# addon.net
KiCad netlist of a schematic drawn in EAGLE
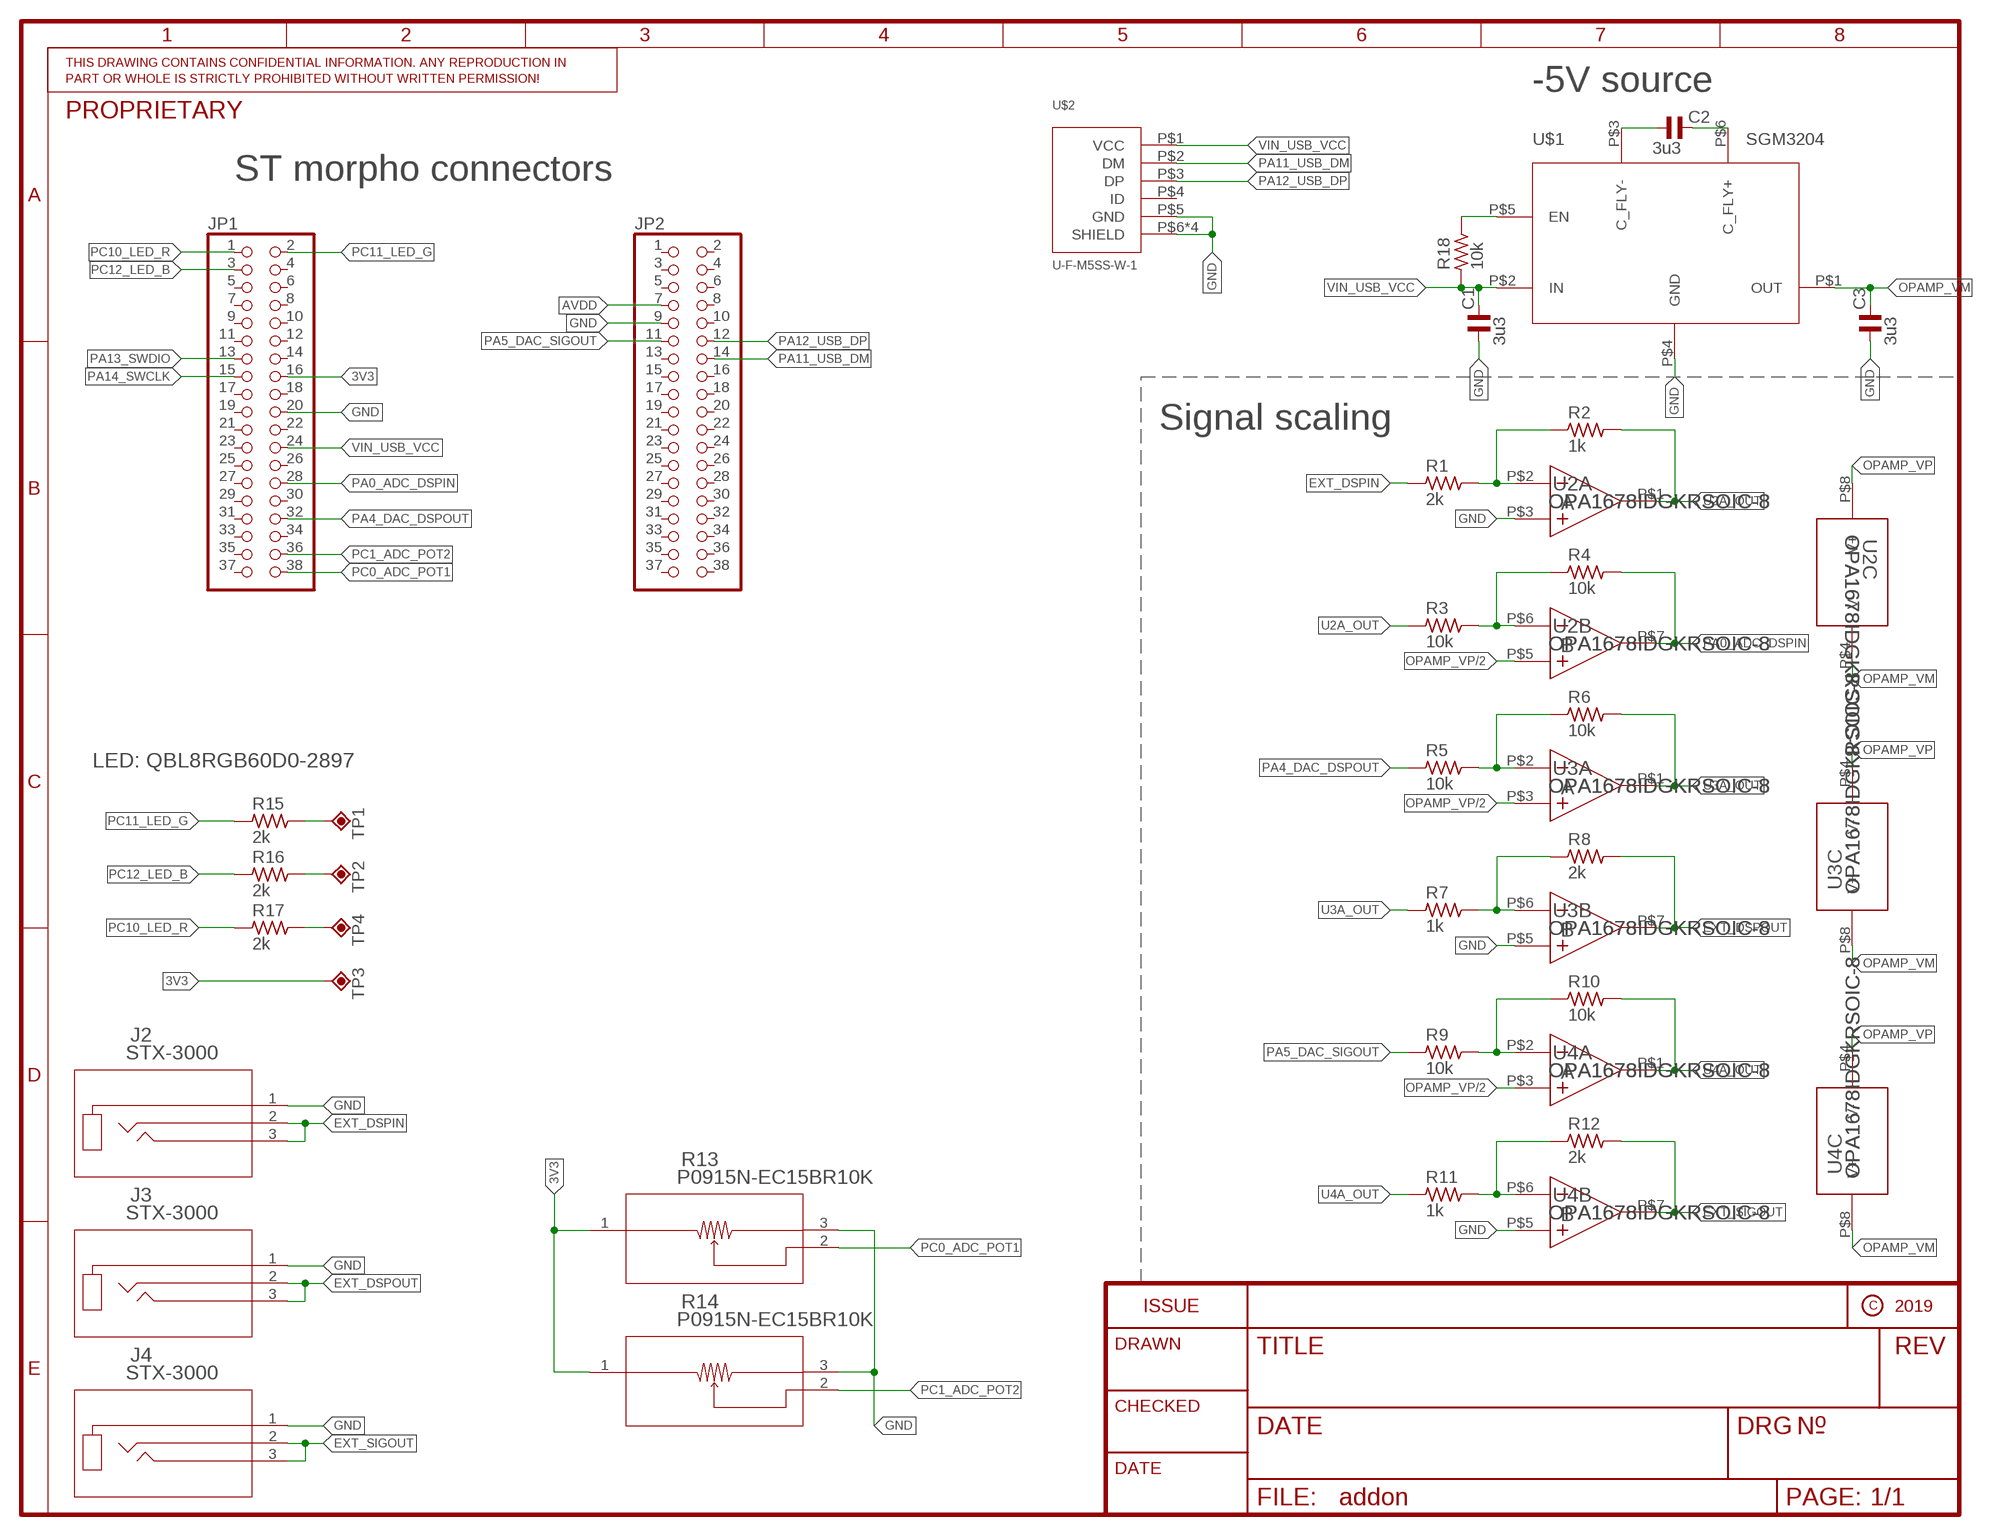
[diagram p0: schematic, sheet 1]

(export (version "E")
  (design (tool "Eeschema 10.0.6"))
  (components
    (comp (ref "C1")
      (value "3u3")
      (footprint "eagle-import:C0603")
      (fields (field (name "PARTNO") "CL10A335KP8NNNC"))
      (libsource (lib "eagle-import") (part "C_0603"))
    )
    (comp (ref "C2")
      (value "3u3")
      (footprint "eagle-import:C0603")
      (fields (field (name "PARTNO") "CL10A335KP8NNNC"))
      (libsource (lib "eagle-import") (part "C_0603"))
    )
    (comp (ref "C3")
      (value "3u3")
      (footprint "eagle-import:C0603")
      (fields (field (name "PARTNO") "CL10A335KP8NNNC"))
      (libsource (lib "eagle-import") (part "C_0603"))
    )
    (comp (ref "J2")
      (value "STX-3000")
      (footprint "eagle-import:STX-3000_KYC")
      (fields (field (name "COPYRIGHT") "Copyright (C) 2018 Accelerated Designs. All rights reserved"))
      (libsource (lib "eagle-import") (part "STX-3000"))
    )
    (comp (ref "J3")
      (value "STX-3000")
      (footprint "eagle-import:STX-3000_KYC")
      (fields (field (name "COPYRIGHT") "Copyright (C) 2018 Accelerated Designs. All rights reserved"))
      (libsource (lib "eagle-import") (part "STX-3000"))
    )
    (comp (ref "J4")
      (value "STX-3000")
      (footprint "eagle-import:STX-3000_KYC")
      (fields (field (name "COPYRIGHT") "Copyright (C) 2018 Accelerated Designs. All rights reserved"))
      (libsource (lib "eagle-import") (part "STX-3000"))
    )
    (comp (ref "JP1")
      (value "PINHD-2X19")
      (footprint "eagle-import:2X19")
      (libsource (lib "eagle-import") (part "PINHD-2X19"))
    )
    (comp (ref "JP2")
      (value "PINHD-2X19")
      (footprint "eagle-import:2X19")
      (libsource (lib "eagle-import") (part "PINHD-2X19"))
    )
    (comp (ref "R1")
      (value "2k")
      (footprint "eagle-import:R0603")
      (libsource (lib "eagle-import") (part "R_0603"))
    )
    (comp (ref "R2")
      (value "1k")
      (footprint "eagle-import:R0603")
      (libsource (lib "eagle-import") (part "R_0603"))
    )
    (comp (ref "R3")
      (value "10k")
      (footprint "eagle-import:R0603")
      (libsource (lib "eagle-import") (part "R_0603"))
    )
    (comp (ref "R4")
      (value "10k")
      (footprint "eagle-import:R0603")
      (libsource (lib "eagle-import") (part "R_0603"))
    )
    (comp (ref "R5")
      (value "10k")
      (footprint "eagle-import:R0603")
      (libsource (lib "eagle-import") (part "R_0603"))
    )
    (comp (ref "R6")
      (value "10k")
      (footprint "eagle-import:R0603")
      (libsource (lib "eagle-import") (part "R_0603"))
    )
    (comp (ref "R7")
      (value "1k")
      (footprint "eagle-import:R0603")
      (libsource (lib "eagle-import") (part "R_0603"))
    )
    (comp (ref "R8")
      (value "2k")
      (footprint "eagle-import:R0603")
      (libsource (lib "eagle-import") (part "R_0603"))
    )
    (comp (ref "R9")
      (value "10k")
      (footprint "eagle-import:R0603")
      (libsource (lib "eagle-import") (part "R_0603"))
    )
    (comp (ref "R10")
      (value "10k")
      (footprint "eagle-import:R0603")
      (libsource (lib "eagle-import") (part "R_0603"))
    )
    (comp (ref "R11")
      (value "1k")
      (footprint "eagle-import:R0603")
      (libsource (lib "eagle-import") (part "R_0603"))
    )
    (comp (ref "R12")
      (value "2k")
      (footprint "eagle-import:R0603")
      (libsource (lib "eagle-import") (part "R_0603"))
    )
    (comp (ref "R13")
      (value "P0915N-EC15BR10K")
      (footprint "eagle-import:P0915N-EC15BR10K_BIT")
      (fields (field (name "COPYRIGHT") "Copyright (C) 2018 Accelerated Designs. All rights reserved"))
      (libsource (lib "eagle-import") (part "P0915N-EC15BR10K"))
    )
    (comp (ref "R14")
      (value "P0915N-EC15BR10K")
      (footprint "eagle-import:P0915N-EC15BR10K_BIT")
      (fields (field (name "COPYRIGHT") "Copyright (C) 2018 Accelerated Designs. All rights reserved"))
      (libsource (lib "eagle-import") (part "P0915N-EC15BR10K"))
    )
    (comp (ref "R15")
      (value "2k")
      (footprint "eagle-import:R0603")
      (libsource (lib "eagle-import") (part "R_0603"))
    )
    (comp (ref "R16")
      (value "2k")
      (footprint "eagle-import:R0603")
      (libsource (lib "eagle-import") (part "R_0603"))
    )
    (comp (ref "R17")
      (value "2k")
      (footprint "eagle-import:R0603")
      (libsource (lib "eagle-import") (part "R_0603"))
    )
    (comp (ref "R18")
      (value "10k")
      (footprint "eagle-import:R0603")
      (libsource (lib "eagle-import") (part "rc-master-smd_R_0603"))
    )
    (comp (ref "TP1")
      (value "TPP-5000-M")
      (footprint "eagle-import:5000-M")
      (libsource (lib "eagle-import") (part "TPP-5000-M"))
    )
    (comp (ref "TP2")
      (value "TPP-5000-M")
      (footprint "eagle-import:5000-M")
      (libsource (lib "eagle-import") (part "TPP-5000-M"))
    )
    (comp (ref "TP3")
      (value "TPP-5000-M")
      (footprint "eagle-import:5000-M")
      (libsource (lib "eagle-import") (part "TPP-5000-M"))
    )
    (comp (ref "TP4")
      (value "TPP-5000-M")
      (footprint "eagle-import:5000-M")
      (libsource (lib "eagle-import") (part "TPP-5000-M"))
    )
    (comp (ref "U$1")
      (value "SGM3204")
      (footprint "eagle-import:SOT-23-6")
      (fields (field (name "PARTNO") "SGM3204YN6G/TR"))
      (libsource (lib "eagle-import") (part "SGM3204"))
    )
    (comp (ref "U$2")
      (value "U-F-M5SS-W-1")
      (footprint "eagle-import:MICRO-B-USB")
      (libsource (lib "eagle-import") (part "U-F-M5SS-W-1"))
    )
    (comp (ref "U2")
      (value "OPA1678IDGKRSOIC-8")
      (footprint "eagle-import:SOIC-8")
      (fields (field (name "PARTNO") "NE5532DR"))
      (libsource (lib "eagle-import") (part "OPA1678IDGKRSOIC-8"))
    )
    (comp (ref "U3")
      (value "OPA1678IDGKRSOIC-8")
      (footprint "eagle-import:SOIC-8")
      (fields (field (name "PARTNO") "NE5532DR"))
      (libsource (lib "eagle-import") (part "OPA1678IDGKRSOIC-8"))
    )
    (comp (ref "U4")
      (value "OPA1678IDGKRSOIC-8")
      (footprint "eagle-import:SOIC-8")
      (fields (field (name "PARTNO") "NE5532DR"))
      (libsource (lib "eagle-import") (part "OPA1678IDGKRSOIC-8"))
    )
  )
  (nets
    (net (code "1") (name "3V3") (class "Default")
      (node (ref "JP1") (pin "16") (pinfunction "16_16") (pintype "passive"))
      (node (ref "R13") (pin "1") (pinfunction "1_1") (pintype "passive"))
      (node (ref "R14") (pin "1") (pinfunction "1_1") (pintype "passive"))
      (node (ref "TP3") (pin "1") (pinfunction "P_1") (pintype "passive"))
    )
    (net (code "2") (name "AVDD") (class "Default")
      (node (ref "JP2") (pin "7") (pinfunction "7_7") (pintype "passive"))
    )
    (net (code "3") (name "EXT_DSPIN") (class "Default")
      (node (ref "J2") (pin "2") (pinfunction "2_2") (pintype "passive"))
      (node (ref "J2") (pin "3") (pinfunction "3_3") (pintype "passive"))
      (node (ref "R1") (pin "1") (pinfunction "1_1") (pintype "passive"))
    )
    (net (code "4") (name "EXT_DSPOUT") (class "Default")
      (node (ref "J3") (pin "2") (pinfunction "2_2") (pintype "passive"))
      (node (ref "J3") (pin "3") (pinfunction "3_3") (pintype "passive"))
      (node (ref "R8") (pin "2") (pinfunction "2_2") (pintype "passive"))
      (node (ref "U3") (pin "P$7") (pinfunction "OUT_P$7") (pintype "output"))
    )
    (net (code "5") (name "EXT_SIGOUT") (class "Default")
      (node (ref "J4") (pin "2") (pinfunction "2_2") (pintype "passive"))
      (node (ref "J4") (pin "3") (pinfunction "3_3") (pintype "passive"))
      (node (ref "R12") (pin "2") (pinfunction "2_2") (pintype "passive"))
      (node (ref "U4") (pin "P$7") (pinfunction "OUT_P$7") (pintype "output"))
    )
    (net (code "6") (name "GND") (class "Default")
      (node (ref "C1") (pin "1") (pinfunction "1_1") (pintype "passive"))
      (node (ref "C3") (pin "1") (pinfunction "1_1") (pintype "passive"))
      (node (ref "J2") (pin "1") (pinfunction "1_1") (pintype "passive"))
      (node (ref "J3") (pin "1") (pinfunction "1_1") (pintype "passive"))
      (node (ref "J4") (pin "1") (pinfunction "1_1") (pintype "passive"))
      (node (ref "JP1") (pin "20") (pinfunction "20_20") (pintype "passive"))
      (node (ref "JP2") (pin "9") (pinfunction "9_9") (pintype "passive"))
      (node (ref "R13") (pin "3") (pinfunction "3_3") (pintype "passive"))
      (node (ref "R14") (pin "3") (pinfunction "3_3") (pintype "passive"))
      (node (ref "U$1") (pin "P$4") (pinfunction "GND_P$4") (pintype "bidirectional"))
      (node (ref "U$2") (pin "P$5") (pinfunction "GND_P$5") (pintype "bidirectional"))
      (node (ref "U$2") (pin "P$6") (pinfunction "SHIELD_P$6") (pintype "bidirectional"))
      (node (ref "U$2") (pin "P$7") (pinfunction "SHIELD_P$7") (pintype "bidirectional"))
      (node (ref "U$2") (pin "P$8") (pinfunction "SHIELD_P$8") (pintype "bidirectional"))
      (node (ref "U$2") (pin "P$9") (pinfunction "SHIELD_P$9") (pintype "bidirectional"))
      (node (ref "U2") (pin "P$3") (pinfunction "IN+_P$3") (pintype "input"))
      (node (ref "U3") (pin "P$5") (pinfunction "IN+_P$5") (pintype "input"))
      (node (ref "U4") (pin "P$5") (pinfunction "IN+_P$5") (pintype "input"))
    )
    (net (code "7") (name "Net-(TP1-P)") (class "Default")
      (node (ref "R15") (pin "2") (pinfunction "2_2") (pintype "passive"))
      (node (ref "TP1") (pin "1") (pinfunction "P_1") (pintype "passive"))
    )
    (net (code "8") (name "Net-(TP2-P)") (class "Default")
      (node (ref "R16") (pin "2") (pinfunction "2_2") (pintype "passive"))
      (node (ref "TP2") (pin "1") (pinfunction "P_1") (pintype "passive"))
    )
    (net (code "9") (name "Net-(TP4-P)") (class "Default")
      (node (ref "R17") (pin "2") (pinfunction "2_2") (pintype "passive"))
      (node (ref "TP4") (pin "1") (pinfunction "P_1") (pintype "passive"))
    )
    (net (code "10") (name "Net-(U$1-C_FLY+)") (class "Default")
      (node (ref "C2") (pin "2") (pinfunction "2_2") (pintype "passive"))
      (node (ref "U$1") (pin "P$6") (pinfunction "C_FLY+_P$6") (pintype "bidirectional"))
    )
    (net (code "11") (name "Net-(U$1-C_FLY-)") (class "Default")
      (node (ref "C2") (pin "1") (pinfunction "1_1") (pintype "passive"))
      (node (ref "U$1") (pin "P$3") (pinfunction "C_FLY-_P$3") (pintype "bidirectional"))
    )
    (net (code "12") (name "Net-(U$1-EN)") (class "Default")
      (node (ref "R18") (pin "2") (pinfunction "2_2") (pintype "passive"))
      (node (ref "U$1") (pin "P$5") (pinfunction "EN_P$5") (pintype "bidirectional"))
    )
    (net (code "13") (name "Net-(U2A-IN-)") (class "Default")
      (node (ref "R1") (pin "2") (pinfunction "2_2") (pintype "passive"))
      (node (ref "R2") (pin "1") (pinfunction "1_1") (pintype "passive"))
      (node (ref "U2") (pin "P$2") (pinfunction "IN-_P$2") (pintype "input"))
    )
    (net (code "14") (name "Net-(U2B-IN-)") (class "Default")
      (node (ref "R3") (pin "2") (pinfunction "2_2") (pintype "passive"))
      (node (ref "R4") (pin "1") (pinfunction "1_1") (pintype "passive"))
      (node (ref "U2") (pin "P$6") (pinfunction "IN-_P$6") (pintype "input"))
    )
    (net (code "15") (name "Net-(U3A-IN-)") (class "Default")
      (node (ref "R5") (pin "2") (pinfunction "2_2") (pintype "passive"))
      (node (ref "R6") (pin "1") (pinfunction "1_1") (pintype "passive"))
      (node (ref "U3") (pin "P$2") (pinfunction "IN-_P$2") (pintype "input"))
    )
    (net (code "16") (name "Net-(U3B-IN-)") (class "Default")
      (node (ref "R7") (pin "2") (pinfunction "2_2") (pintype "passive"))
      (node (ref "R8") (pin "1") (pinfunction "1_1") (pintype "passive"))
      (node (ref "U3") (pin "P$6") (pinfunction "IN-_P$6") (pintype "input"))
    )
    (net (code "17") (name "Net-(U4A-IN-)") (class "Default")
      (node (ref "R10") (pin "1") (pinfunction "1_1") (pintype "passive"))
      (node (ref "R9") (pin "2") (pinfunction "2_2") (pintype "passive"))
      (node (ref "U4") (pin "P$2") (pinfunction "IN-_P$2") (pintype "input"))
    )
    (net (code "18") (name "Net-(U4B-IN-)") (class "Default")
      (node (ref "R11") (pin "2") (pinfunction "2_2") (pintype "passive"))
      (node (ref "R12") (pin "1") (pinfunction "1_1") (pintype "passive"))
      (node (ref "U4") (pin "P$6") (pinfunction "IN-_P$6") (pintype "input"))
    )
    (net (code "19") (name "OPAMP_VM") (class "Default")
      (node (ref "C3") (pin "2") (pinfunction "2_2") (pintype "passive"))
      (node (ref "U$1") (pin "P$1") (pinfunction "OUT_P$1") (pintype "bidirectional"))
      (node (ref "U2") (pin "P$4") (pinfunction "V-_P$4") (pintype "power_in"))
      (node (ref "U3") (pin "P$8") (pinfunction "V+_P$8") (pintype "power_in"))
      (node (ref "U4") (pin "P$8") (pinfunction "V+_P$8") (pintype "power_in"))
    )
    (net (code "20") (name "OPAMP_VP") (class "Default")
      (node (ref "U2") (pin "P$8") (pinfunction "V+_P$8") (pintype "power_in"))
      (node (ref "U3") (pin "P$4") (pinfunction "V-_P$4") (pintype "power_in"))
      (node (ref "U4") (pin "P$4") (pinfunction "V-_P$4") (pintype "power_in"))
    )
    (net (code "21") (name "OPAMP_VP{slash}2") (class "Default")
      (node (ref "U2") (pin "P$5") (pinfunction "IN+_P$5") (pintype "input"))
      (node (ref "U3") (pin "P$3") (pinfunction "IN+_P$3") (pintype "input"))
      (node (ref "U4") (pin "P$3") (pinfunction "IN+_P$3") (pintype "input"))
    )
    (net (code "22") (name "PA0_ADC_DSPIN") (class "Default")
      (node (ref "JP1") (pin "28") (pinfunction "28_28") (pintype "passive"))
      (node (ref "R4") (pin "2") (pinfunction "2_2") (pintype "passive"))
      (node (ref "U2") (pin "P$7") (pinfunction "OUT_P$7") (pintype "output"))
    )
    (net (code "23") (name "PA4_DAC_DSPOUT") (class "Default")
      (node (ref "JP1") (pin "32") (pinfunction "32_32") (pintype "passive"))
      (node (ref "R5") (pin "1") (pinfunction "1_1") (pintype "passive"))
    )
    (net (code "24") (name "PA5_DAC_SIGOUT") (class "Default")
      (node (ref "JP2") (pin "11") (pinfunction "11_11") (pintype "passive"))
      (node (ref "R9") (pin "1") (pinfunction "1_1") (pintype "passive"))
    )
    (net (code "25") (name "PA11_USB_DM") (class "Default")
      (node (ref "JP2") (pin "14") (pinfunction "14_14") (pintype "passive"))
      (node (ref "U$2") (pin "P$2") (pinfunction "DM_P$2") (pintype "bidirectional"))
    )
    (net (code "26") (name "PA12_USB_DP") (class "Default")
      (node (ref "JP2") (pin "12") (pinfunction "12_12") (pintype "passive"))
      (node (ref "U$2") (pin "P$3") (pinfunction "DP_P$3") (pintype "bidirectional"))
    )
    (net (code "27") (name "PA13_SWDIO") (class "Default")
      (node (ref "JP1") (pin "13") (pinfunction "13_13") (pintype "passive"))
    )
    (net (code "28") (name "PA14_SWCLK") (class "Default")
      (node (ref "JP1") (pin "15") (pinfunction "15_15") (pintype "passive"))
    )
    (net (code "29") (name "PC0_ADC_POT1") (class "Default")
      (node (ref "JP1") (pin "38") (pinfunction "38_38") (pintype "passive"))
      (node (ref "R13") (pin "2") (pinfunction "2_2") (pintype "passive"))
    )
    (net (code "30") (name "PC1_ADC_POT2") (class "Default")
      (node (ref "JP1") (pin "36") (pinfunction "36_36") (pintype "passive"))
      (node (ref "R14") (pin "2") (pinfunction "2_2") (pintype "passive"))
    )
    (net (code "31") (name "PC10_LED_R") (class "Default")
      (node (ref "JP1") (pin "1") (pinfunction "1_1") (pintype "passive"))
      (node (ref "R17") (pin "1") (pinfunction "1_1") (pintype "passive"))
    )
    (net (code "32") (name "PC11_LED_G") (class "Default")
      (node (ref "JP1") (pin "2") (pinfunction "2_2") (pintype "passive"))
      (node (ref "R15") (pin "1") (pinfunction "1_1") (pintype "passive"))
    )
    (net (code "33") (name "PC12_LED_B") (class "Default")
      (node (ref "JP1") (pin "3") (pinfunction "3_3") (pintype "passive"))
      (node (ref "R16") (pin "1") (pinfunction "1_1") (pintype "passive"))
    )
    (net (code "34") (name "U2A_OUT") (class "Default")
      (node (ref "R2") (pin "2") (pinfunction "2_2") (pintype "passive"))
      (node (ref "R3") (pin "1") (pinfunction "1_1") (pintype "passive"))
      (node (ref "U2") (pin "P$1") (pinfunction "OUT_P$1") (pintype "output"))
    )
    (net (code "35") (name "U3A_OUT") (class "Default")
      (node (ref "R6") (pin "2") (pinfunction "2_2") (pintype "passive"))
      (node (ref "R7") (pin "1") (pinfunction "1_1") (pintype "passive"))
      (node (ref "U3") (pin "P$1") (pinfunction "OUT_P$1") (pintype "output"))
    )
    (net (code "36") (name "U4A_OUT") (class "Default")
      (node (ref "R10") (pin "2") (pinfunction "2_2") (pintype "passive"))
      (node (ref "R11") (pin "1") (pinfunction "1_1") (pintype "passive"))
      (node (ref "U4") (pin "P$1") (pinfunction "OUT_P$1") (pintype "output"))
    )
    (net (code "37") (name "VIN_USB_VCC") (class "Default")
      (node (ref "C1") (pin "2") (pinfunction "2_2") (pintype "passive"))
      (node (ref "JP1") (pin "24") (pinfunction "24_24") (pintype "passive"))
      (node (ref "R18") (pin "1") (pinfunction "1_1") (pintype "passive"))
      (node (ref "U$1") (pin "P$2") (pinfunction "IN_P$2") (pintype "bidirectional"))
      (node (ref "U$2") (pin "P$1") (pinfunction "VCC_P$1") (pintype "bidirectional"))
    )
    (net (code "38") (name "unconnected-(JP1-Pad4)") (class "Default")
      (node (ref "JP1") (pin "4") (pinfunction "4_4") (pintype "passive"))
    )
    (net (code "39") (name "unconnected-(JP1-Pad5)") (class "Default")
      (node (ref "JP1") (pin "5") (pinfunction "5_5") (pintype "passive"))
    )
    (net (code "40") (name "unconnected-(JP1-Pad6)") (class "Default")
      (node (ref "JP1") (pin "6") (pinfunction "6_6") (pintype "passive"))
    )
    (net (code "41") (name "unconnected-(JP1-Pad7)") (class "Default")
      (node (ref "JP1") (pin "7") (pinfunction "7_7") (pintype "passive"))
    )
    (net (code "42") (name "unconnected-(JP1-Pad8)") (class "Default")
      (node (ref "JP1") (pin "8") (pinfunction "8_8") (pintype "passive"))
    )
    (net (code "43") (name "unconnected-(JP1-Pad9)") (class "Default")
      (node (ref "JP1") (pin "9") (pinfunction "9_9") (pintype "passive"))
    )
    (net (code "44") (name "unconnected-(JP1-Pad10)") (class "Default")
      (node (ref "JP1") (pin "10") (pinfunction "10_10") (pintype "passive"))
    )
    (net (code "45") (name "unconnected-(JP1-Pad11)") (class "Default")
      (node (ref "JP1") (pin "11") (pinfunction "11_11") (pintype "passive"))
    )
    (net (code "46") (name "unconnected-(JP1-Pad12)") (class "Default")
      (node (ref "JP1") (pin "12") (pinfunction "12_12") (pintype "passive"))
    )
    (net (code "47") (name "unconnected-(JP1-Pad14)") (class "Default")
      (node (ref "JP1") (pin "14") (pinfunction "14_14") (pintype "passive"))
    )
    (net (code "48") (name "unconnected-(JP1-Pad17)") (class "Default")
      (node (ref "JP1") (pin "17") (pinfunction "17_17") (pintype "passive"))
    )
    (net (code "49") (name "unconnected-(JP1-Pad18)") (class "Default")
      (node (ref "JP1") (pin "18") (pinfunction "18_18") (pintype "passive"))
    )
    (net (code "50") (name "unconnected-(JP1-Pad19)") (class "Default")
      (node (ref "JP1") (pin "19") (pinfunction "19_19") (pintype "passive"))
    )
    (net (code "51") (name "unconnected-(JP1-Pad21)") (class "Default")
      (node (ref "JP1") (pin "21") (pinfunction "21_21") (pintype "passive"))
    )
    (net (code "52") (name "unconnected-(JP1-Pad22)") (class "Default")
      (node (ref "JP1") (pin "22") (pinfunction "22_22") (pintype "passive"))
    )
    (net (code "53") (name "unconnected-(JP1-Pad23)") (class "Default")
      (node (ref "JP1") (pin "23") (pinfunction "23_23") (pintype "passive"))
    )
    (net (code "54") (name "unconnected-(JP1-Pad25)") (class "Default")
      (node (ref "JP1") (pin "25") (pinfunction "25_25") (pintype "passive"))
    )
    (net (code "55") (name "unconnected-(JP1-Pad26)") (class "Default")
      (node (ref "JP1") (pin "26") (pinfunction "26_26") (pintype "passive"))
    )
    (net (code "56") (name "unconnected-(JP1-Pad27)") (class "Default")
      (node (ref "JP1") (pin "27") (pinfunction "27_27") (pintype "passive"))
    )
    (net (code "57") (name "unconnected-(JP1-Pad29)") (class "Default")
      (node (ref "JP1") (pin "29") (pinfunction "29_29") (pintype "passive"))
    )
    (net (code "58") (name "unconnected-(JP1-Pad30)") (class "Default")
      (node (ref "JP1") (pin "30") (pinfunction "30_30") (pintype "passive"))
    )
    (net (code "59") (name "unconnected-(JP1-Pad31)") (class "Default")
      (node (ref "JP1") (pin "31") (pinfunction "31_31") (pintype "passive"))
    )
    (net (code "60") (name "unconnected-(JP1-Pad33)") (class "Default")
      (node (ref "JP1") (pin "33") (pinfunction "33_33") (pintype "passive"))
    )
    (net (code "61") (name "unconnected-(JP1-Pad34)") (class "Default")
      (node (ref "JP1") (pin "34") (pinfunction "34_34") (pintype "passive"))
    )
    (net (code "62") (name "unconnected-(JP1-Pad35)") (class "Default")
      (node (ref "JP1") (pin "35") (pinfunction "35_35") (pintype "passive"))
    )
    (net (code "63") (name "unconnected-(JP1-Pad37)") (class "Default")
      (node (ref "JP1") (pin "37") (pinfunction "37_37") (pintype "passive"))
    )
    (net (code "64") (name "unconnected-(JP2-Pad1)") (class "Default")
      (node (ref "JP2") (pin "1") (pinfunction "1_1") (pintype "passive"))
    )
    (net (code "65") (name "unconnected-(JP2-Pad2)") (class "Default")
      (node (ref "JP2") (pin "2") (pinfunction "2_2") (pintype "passive"))
    )
    (net (code "66") (name "unconnected-(JP2-Pad3)") (class "Default")
      (node (ref "JP2") (pin "3") (pinfunction "3_3") (pintype "passive"))
    )
    (net (code "67") (name "unconnected-(JP2-Pad4)") (class "Default")
      (node (ref "JP2") (pin "4") (pinfunction "4_4") (pintype "passive"))
    )
    (net (code "68") (name "unconnected-(JP2-Pad5)") (class "Default")
      (node (ref "JP2") (pin "5") (pinfunction "5_5") (pintype "passive"))
    )
    (net (code "69") (name "unconnected-(JP2-Pad6)") (class "Default")
      (node (ref "JP2") (pin "6") (pinfunction "6_6") (pintype "passive"))
    )
    (net (code "70") (name "unconnected-(JP2-Pad8)") (class "Default")
      (node (ref "JP2") (pin "8") (pinfunction "8_8") (pintype "passive"))
    )
    (net (code "71") (name "unconnected-(JP2-Pad10)") (class "Default")
      (node (ref "JP2") (pin "10") (pinfunction "10_10") (pintype "passive"))
    )
    (net (code "72") (name "unconnected-(JP2-Pad13)") (class "Default")
      (node (ref "JP2") (pin "13") (pinfunction "13_13") (pintype "passive"))
    )
    (net (code "73") (name "unconnected-(JP2-Pad15)") (class "Default")
      (node (ref "JP2") (pin "15") (pinfunction "15_15") (pintype "passive"))
    )
    (net (code "74") (name "unconnected-(JP2-Pad16)") (class "Default")
      (node (ref "JP2") (pin "16") (pinfunction "16_16") (pintype "passive"))
    )
    (net (code "75") (name "unconnected-(JP2-Pad17)") (class "Default")
      (node (ref "JP2") (pin "17") (pinfunction "17_17") (pintype "passive"))
    )
    (net (code "76") (name "unconnected-(JP2-Pad18)") (class "Default")
      (node (ref "JP2") (pin "18") (pinfunction "18_18") (pintype "passive"))
    )
    (net (code "77") (name "unconnected-(JP2-Pad19)") (class "Default")
      (node (ref "JP2") (pin "19") (pinfunction "19_19") (pintype "passive"))
    )
    (net (code "78") (name "unconnected-(JP2-Pad20)") (class "Default")
      (node (ref "JP2") (pin "20") (pinfunction "20_20") (pintype "passive"))
    )
    (net (code "79") (name "unconnected-(JP2-Pad21)") (class "Default")
      (node (ref "JP2") (pin "21") (pinfunction "21_21") (pintype "passive"))
    )
    (net (code "80") (name "unconnected-(JP2-Pad22)") (class "Default")
      (node (ref "JP2") (pin "22") (pinfunction "22_22") (pintype "passive"))
    )
    (net (code "81") (name "unconnected-(JP2-Pad23)") (class "Default")
      (node (ref "JP2") (pin "23") (pinfunction "23_23") (pintype "passive"))
    )
    (net (code "82") (name "unconnected-(JP2-Pad24)") (class "Default")
      (node (ref "JP2") (pin "24") (pinfunction "24_24") (pintype "passive"))
    )
    (net (code "83") (name "unconnected-(JP2-Pad25)") (class "Default")
      (node (ref "JP2") (pin "25") (pinfunction "25_25") (pintype "passive"))
    )
    (net (code "84") (name "unconnected-(JP2-Pad26)") (class "Default")
      (node (ref "JP2") (pin "26") (pinfunction "26_26") (pintype "passive"))
    )
    (net (code "85") (name "unconnected-(JP2-Pad27)") (class "Default")
      (node (ref "JP2") (pin "27") (pinfunction "27_27") (pintype "passive"))
    )
    (net (code "86") (name "unconnected-(JP2-Pad28)") (class "Default")
      (node (ref "JP2") (pin "28") (pinfunction "28_28") (pintype "passive"))
    )
    (net (code "87") (name "unconnected-(JP2-Pad29)") (class "Default")
      (node (ref "JP2") (pin "29") (pinfunction "29_29") (pintype "passive"))
    )
    (net (code "88") (name "unconnected-(JP2-Pad30)") (class "Default")
      (node (ref "JP2") (pin "30") (pinfunction "30_30") (pintype "passive"))
    )
    (net (code "89") (name "unconnected-(JP2-Pad31)") (class "Default")
      (node (ref "JP2") (pin "31") (pinfunction "31_31") (pintype "passive"))
    )
    (net (code "90") (name "unconnected-(JP2-Pad32)") (class "Default")
      (node (ref "JP2") (pin "32") (pinfunction "32_32") (pintype "passive"))
    )
    (net (code "91") (name "unconnected-(JP2-Pad33)") (class "Default")
      (node (ref "JP2") (pin "33") (pinfunction "33_33") (pintype "passive"))
    )
    (net (code "92") (name "unconnected-(JP2-Pad34)") (class "Default")
      (node (ref "JP2") (pin "34") (pinfunction "34_34") (pintype "passive"))
    )
    (net (code "93") (name "unconnected-(JP2-Pad35)") (class "Default")
      (node (ref "JP2") (pin "35") (pinfunction "35_35") (pintype "passive"))
    )
    (net (code "94") (name "unconnected-(JP2-Pad36)") (class "Default")
      (node (ref "JP2") (pin "36") (pinfunction "36_36") (pintype "passive"))
    )
    (net (code "95") (name "unconnected-(JP2-Pad37)") (class "Default")
      (node (ref "JP2") (pin "37") (pinfunction "37_37") (pintype "passive"))
    )
    (net (code "96") (name "unconnected-(JP2-Pad38)") (class "Default")
      (node (ref "JP2") (pin "38") (pinfunction "38_38") (pintype "passive"))
    )
    (net (code "97") (name "unconnected-(U$2-ID-PadP$4)") (class "Default")
      (node (ref "U$2") (pin "P$4") (pinfunction "ID_P$4") (pintype "bidirectional"))
    )
  )
)
